# AnalogMeas.net
KiCad netlist of a schematic drawn in Altium Designer
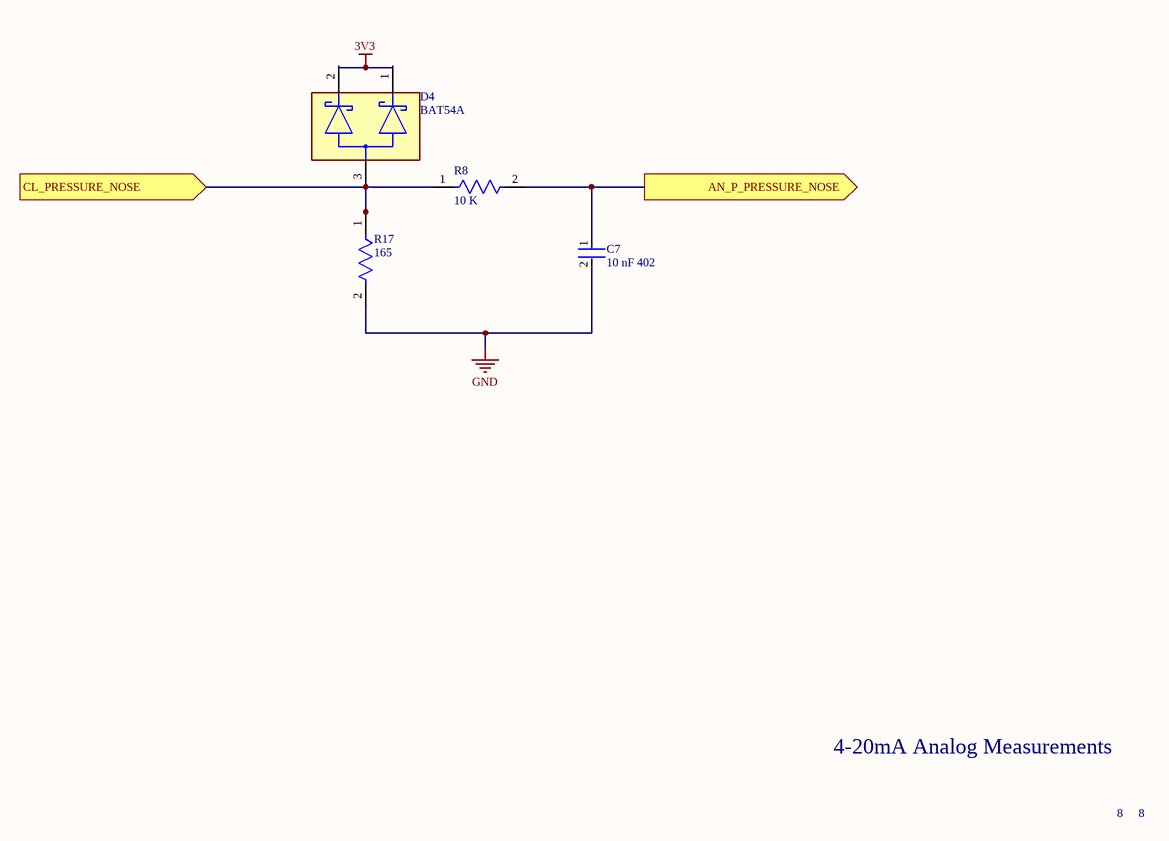
[diagram p0:  AnalogMeas.SchDoc]

(export (version "E")
  (design (tool "Eeschema 10.0.6"))
  (components
    (comp (ref "C7")
      (value "10 nF 402")
      (footprint "FP-GJM155-0_05-IPC_C")
      (description "Multi-Layer Ceramic Capacitor 0.75pF C0G  ±0.1pF 0402 Paper T/R")
      (libsource (lib "Altium Content Vault") (part "02cd4be3c70576c341d710602a673aa"))
    )
    (comp (ref "D4")
      (value "BAT54A")
      (footprint "FP-BAT54A-IPC_B")
      (description "Schottky Diodes & Rectifiers SOT23CA.0.2A 30V Sch ottky")
      (libsource (lib "Altium Content Vault") (part "690febdc862f2b377fafde756ecfdda"))
    )
    (comp (ref "R8")
      (value "10 K")
      (footprint "FP-RP73P-1E-MFG")
      (description "RP73P 0402 165Ω 0.1W 25ppm/°C 0.10% 50V")
      (fields
        (field (name "OCTOPART") "https://octopart.com/rp73pf1e165rbtd-te+connectivity-89229973")
        (field (name "MANUFACTURER PART NUMBER") "RP73PF1E165RBTD")
      )
      (libsource (lib "Altium Content Vault") (part "1029c3af85768c4190bb7ad29bc67b5"))
    )
    (comp (ref "R17")
      (value "165")
      (footprint "FP-RP73P-1E-MFG")
      (description "RP73P 0402 165Ω 0.1W 25ppm/°C 0.10% 50V")
      (fields
        (field (name "OCTOPART") "https://octopart.com/rp73pf1e165rbtd-te+connectivity-89229973")
        (field (name "MANUFACTURER PART NUMBER") "RP73PF1E165RBTD")
      )
      (libsource (lib "Altium Content Vault") (part "1029c3af85768c4190bb7ad29bc67b5"))
    )
  )
  (nets
    (net (code "1") (name "/AN_P_PRESSURE_NOSE") (class "Default")
      (node (ref "C7") (pin "1") (pinfunction "1_1") (pintype "passive"))
      (node (ref "R8") (pin "2") (pinfunction "2_2") (pintype "passive"))
    )
    (net (code "2") (name "/CL_PRESSURE_NOSE") (class "Default")
      (node (ref "D4") (pin "3") (pinfunction "COMMON_ANODE_3") (pintype "passive"))
      (node (ref "R17") (pin "1") (pinfunction "1_1") (pintype "passive"))
      (node (ref "R8") (pin "1") (pinfunction "1_1") (pintype "passive"))
    )
    (net (code "3") (name "3V3") (class "Default")
      (node (ref "D4") (pin "1") (pinfunction "1_CATHODE_1") (pintype "passive"))
      (node (ref "D4") (pin "2") (pinfunction "2_CATHODE_2") (pintype "passive"))
    )
    (net (code "4") (name "GND") (class "Default")
      (node (ref "C7") (pin "2") (pinfunction "2_2") (pintype "passive"))
      (node (ref "R17") (pin "2") (pinfunction "2_2") (pintype "passive"))
    )
  )
)
